# v.net
KiCad netlist of a schematic drawn in EasyEDA
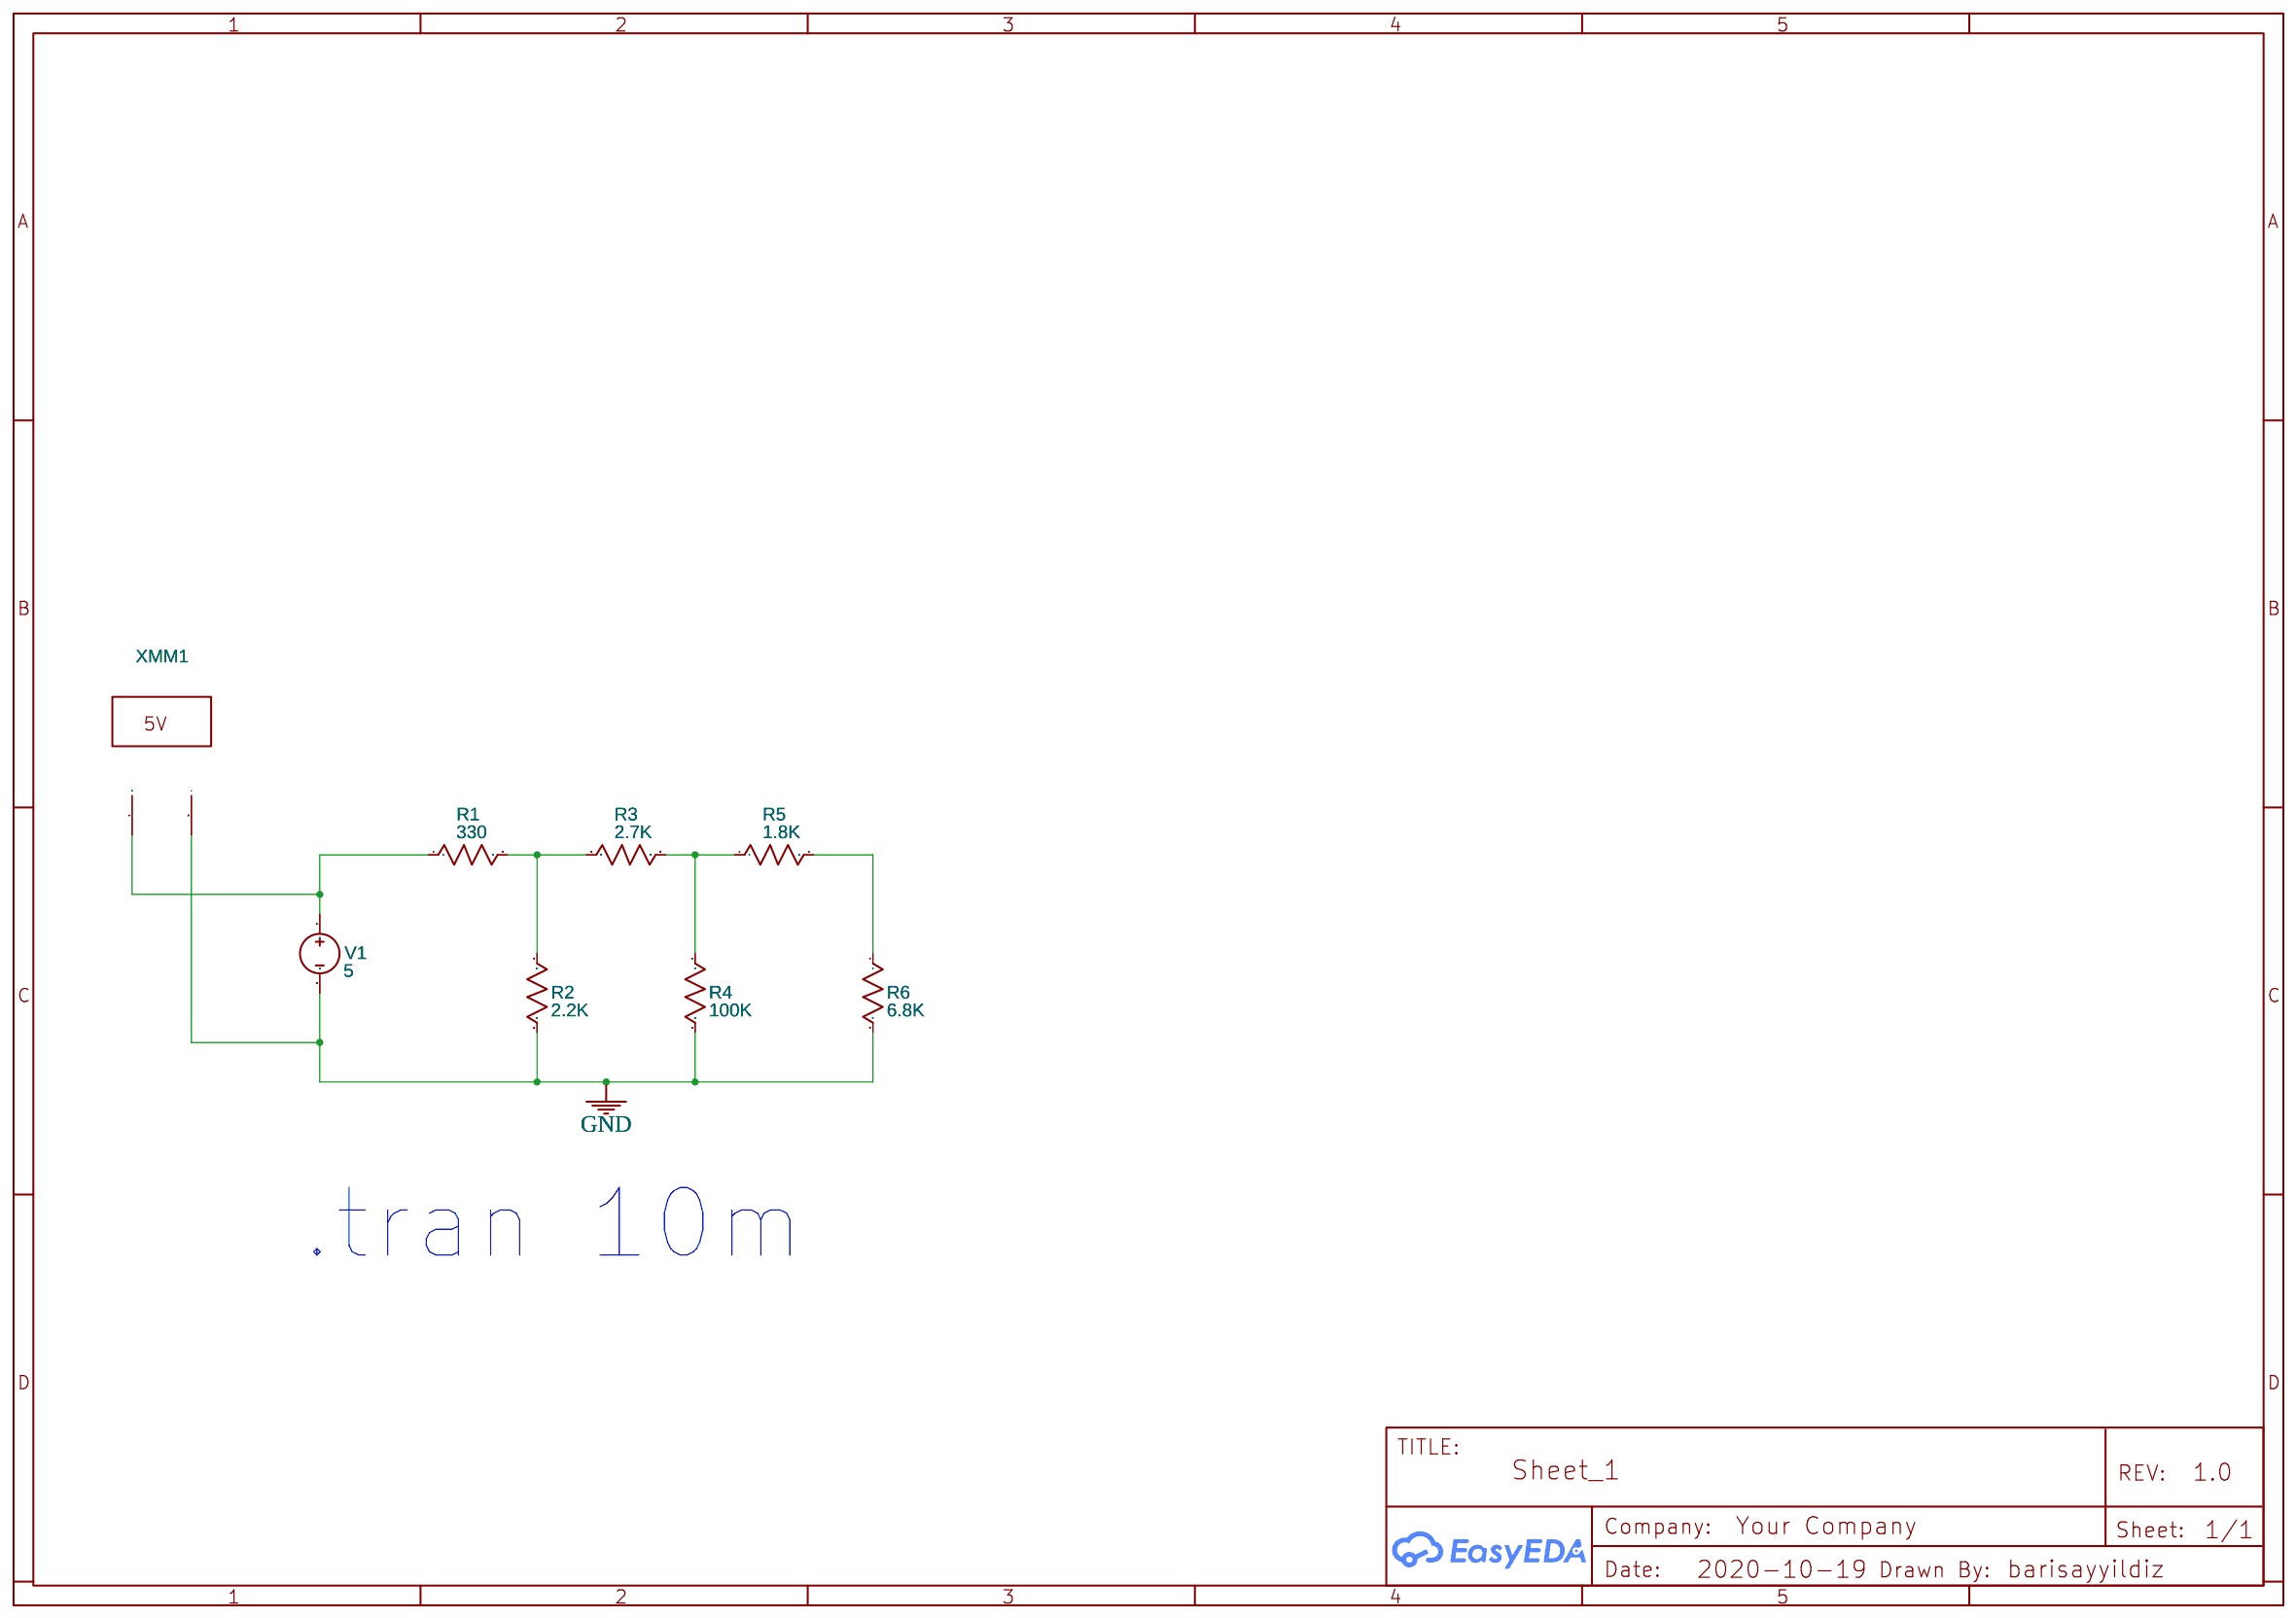
[diagram p0: schematic sheet]

(export (version "E")
  (design (tool "Eeschema 10.0.6"))
  (components
    (comp (ref "R1") (value "330") (libsource (lib "") (part "Resistor_US_1")))
    (comp (ref "R2") (value "2.2K") (libsource (lib "") (part "Resistor_US")))
    (comp (ref "R3") (value "2.7K") (libsource (lib "") (part "Resistor_US_1")))
    (comp (ref "R4") (value "100K") (libsource (lib "") (part "Resistor_US")))
    (comp (ref "R5") (value "1.8K") (libsource (lib "") (part "Resistor_US_1")))
    (comp (ref "R6") (value "6.8K") (libsource (lib "") (part "Resistor_US")))
    (comp (ref "V1") (value "5") (libsource (lib "") (part "VDC")))
    (comp (ref "XMM1") (value "Multimeter") (libsource (lib "") (part "MULTIMETER")))
  )
  (nets
    (net (code "1") (name "GND") (class "Default")
      (node (ref "R2") (pin "2") (pinfunction "2_2") (pintype "unspecified"))
      (node (ref "R4") (pin "2") (pinfunction "2_2") (pintype "unspecified"))
      (node (ref "R6") (pin "2") (pinfunction "2_2") (pintype "unspecified"))
      (node (ref "V1") (pin "2") (pinfunction "2_2") (pintype "unspecified"))
      (node (ref "XMM1") (pin "2") (pinfunction "I_2") (pintype "unspecified"))
    )
    (net (code "2") (name "Net-(R1-Pad2)") (class "Default")
      (node (ref "R1") (pin "2") (pinfunction "2_2") (pintype "unspecified"))
      (node (ref "R2") (pin "1") (pinfunction "1_1") (pintype "unspecified"))
      (node (ref "R3") (pin "1") (pinfunction "1_1") (pintype "unspecified"))
    )
    (net (code "3") (name "Net-(R3-Pad2)") (class "Default")
      (node (ref "R3") (pin "2") (pinfunction "2_2") (pintype "unspecified"))
      (node (ref "R4") (pin "1") (pinfunction "1_1") (pintype "unspecified"))
      (node (ref "R5") (pin "1") (pinfunction "1_1") (pintype "unspecified"))
    )
    (net (code "4") (name "Net-(R5-Pad2)") (class "Default")
      (node (ref "R5") (pin "2") (pinfunction "2_2") (pintype "unspecified"))
      (node (ref "R6") (pin "1") (pinfunction "1_1") (pintype "unspecified"))
    )
    (net (code "5") (name "Net-(XMM1-+)") (class "Default")
      (node (ref "R1") (pin "1") (pinfunction "1_1") (pintype "unspecified"))
      (node (ref "V1") (pin "1") (pinfunction "1_1") (pintype "unspecified"))
      (node (ref "XMM1") (pin "1") (pinfunction "+_1") (pintype "unspecified"))
    )
  )
)
